# nuksh.net
KiCad netlist of a schematic drawn in EAGLE
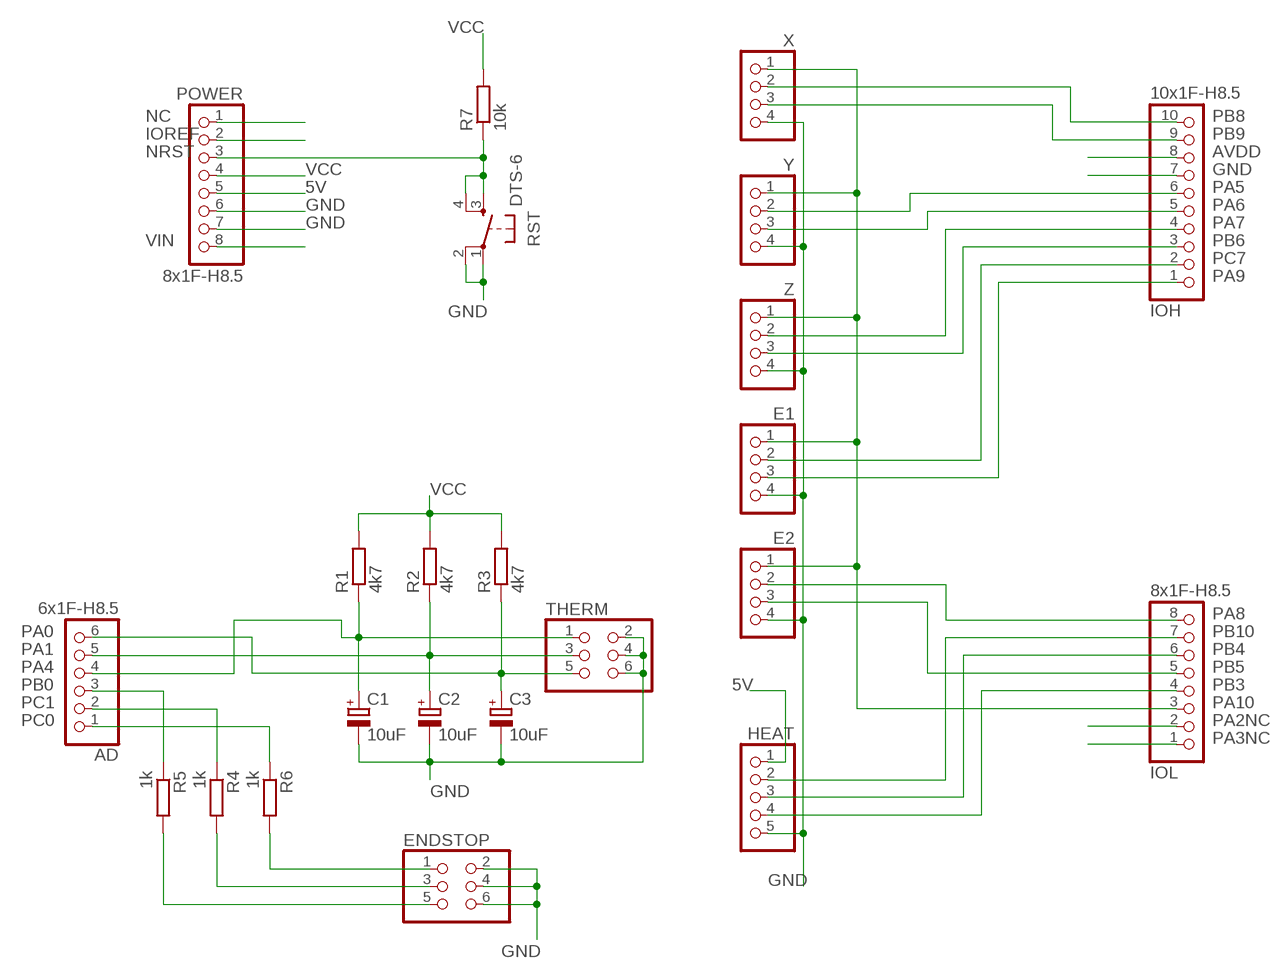
[diagram p0: schematic, sheet 1]

(export (version "E")
  (design (tool "Eeschema 10.0.6"))
  (components
    (comp (ref "AD")
      (value "6x1F-H8.5")
      (footprint "eagle-import:1X06")
      (libsource (lib "eagle-import") (part "PINHD-1X6"))
    )
    (comp (ref "C1")
      (value "10uF")
      (footprint "eagle-import:153CLV-0605")
      (libsource (lib "eagle-import") (part "CPOL-EU153CLV-0605"))
    )
    (comp (ref "C2")
      (value "10uF")
      (footprint "eagle-import:153CLV-0605")
      (libsource (lib "eagle-import") (part "CPOL-EU153CLV-0605"))
    )
    (comp (ref "C3")
      (value "10uF")
      (footprint "eagle-import:153CLV-0605")
      (libsource (lib "eagle-import") (part "CPOL-EU153CLV-0605"))
    )
    (comp (ref "E1")
      (value "PINHD-1X4")
      (footprint "eagle-import:1X04")
      (libsource (lib "eagle-import") (part "PINHD-1X4"))
    )
    (comp (ref "E2")
      (value "PINHD-1X4")
      (footprint "eagle-import:1X04")
      (libsource (lib "eagle-import") (part "PINHD-1X4"))
    )
    (comp (ref "ENDSTOP")
      (value "PINHD-2X3")
      (footprint "eagle-import:2X03")
      (libsource (lib "eagle-import") (part "PINHD-2X3"))
    )
    (comp (ref "HEAT")
      (value "PINHD-1X5")
      (footprint "eagle-import:1X05")
      (libsource (lib "eagle-import") (part "PINHD-1X5"))
    )
    (comp (ref "IOH")
      (value "10x1F-H8.5")
      (footprint "eagle-import:1X10")
      (libsource (lib "eagle-import") (part "PINHD-1X10_ARD"))
    )
    (comp (ref "IOL")
      (value "8x1F-H8.5")
      (footprint "eagle-import:1X08")
      (libsource (lib "eagle-import") (part "PINHD-1X8"))
    )
    (comp (ref "POWER")
      (value "8x1F-H8.5")
      (footprint "eagle-import:1X08")
      (libsource (lib "eagle-import") (part "PINHD-1X8"))
    )
    (comp (ref "R1")
      (value "4k7")
      (footprint "eagle-import:R0805")
      (libsource (lib "eagle-import") (part "R-EU_R0805"))
    )
    (comp (ref "R2")
      (value "4k7")
      (footprint "eagle-import:R0805")
      (libsource (lib "eagle-import") (part "R-EU_R0805"))
    )
    (comp (ref "R3")
      (value "4k7")
      (footprint "eagle-import:R0805")
      (libsource (lib "eagle-import") (part "R-EU_R0805"))
    )
    (comp (ref "R4")
      (value "1k")
      (footprint "eagle-import:R0805")
      (libsource (lib "eagle-import") (part "R-EU_R0805"))
    )
    (comp (ref "R5")
      (value "1k")
      (footprint "eagle-import:R0805")
      (libsource (lib "eagle-import") (part "R-EU_R0805"))
    )
    (comp (ref "R6")
      (value "1k")
      (footprint "eagle-import:R0805")
      (libsource (lib "eagle-import") (part "R-EU_R0805"))
    )
    (comp (ref "R7")
      (value "10k")
      (footprint "eagle-import:R0805")
      (libsource (lib "eagle-import") (part "R-EU_R0805"))
    )
    (comp (ref "RST")
      (value "DTS-6")
      (footprint "eagle-import:DTS-6")
      (libsource (lib "eagle-import") (part "DTS-6"))
    )
    (comp (ref "THERM")
      (value "PINHD-2X3")
      (footprint "eagle-import:2X03")
      (libsource (lib "eagle-import") (part "PINHD-2X3"))
    )
    (comp (ref "X")
      (value "PINHD-1X4")
      (footprint "eagle-import:1X04")
      (libsource (lib "eagle-import") (part "PINHD-1X4"))
    )
    (comp (ref "Y")
      (value "PINHD-1X4")
      (footprint "eagle-import:1X04")
      (libsource (lib "eagle-import") (part "PINHD-1X4"))
    )
    (comp (ref "Z")
      (value "PINHD-1X4")
      (footprint "eagle-import:1X04")
      (libsource (lib "eagle-import") (part "PINHD-1X4"))
    )
  )
  (nets
    (net (code "1") (name "/5V") (class "Default")
      (node (ref "HEAT") (pin "1") (pinfunction "1_1") (pintype "passive"))
      (node (ref "POWER") (pin "5") (pinfunction "5_5") (pintype "passive"))
    )
    (net (code "2") (name "/AVDD") (class "Default")
      (node (ref "IOH") (pin "8") (pinfunction "8_8") (pintype "passive"))
    )
    (net (code "3") (name "/GND") (class "Default")
      (node (ref "C1") (pin "-") (pinfunction "-_-") (pintype "passive"))
      (node (ref "C2") (pin "-") (pinfunction "-_-") (pintype "passive"))
      (node (ref "C3") (pin "-") (pinfunction "-_-") (pintype "passive"))
      (node (ref "E1") (pin "4") (pinfunction "4_4") (pintype "passive"))
      (node (ref "E2") (pin "4") (pinfunction "4_4") (pintype "passive"))
      (node (ref "ENDSTOP") (pin "2") (pinfunction "2_2") (pintype "passive"))
      (node (ref "ENDSTOP") (pin "4") (pinfunction "4_4") (pintype "passive"))
      (node (ref "ENDSTOP") (pin "6") (pinfunction "6_6") (pintype "passive"))
      (node (ref "HEAT") (pin "5") (pinfunction "5_5") (pintype "passive"))
      (node (ref "IOH") (pin "7") (pinfunction "7_7") (pintype "passive"))
      (node (ref "POWER") (pin "6") (pinfunction "6_6") (pintype "passive"))
      (node (ref "POWER") (pin "7") (pinfunction "7_7") (pintype "passive"))
      (node (ref "RST") (pin "1") (pinfunction "1_1") (pintype "passive"))
      (node (ref "RST") (pin "2") (pinfunction "2_2") (pintype "passive"))
      (node (ref "THERM") (pin "2") (pinfunction "2_2") (pintype "passive"))
      (node (ref "THERM") (pin "4") (pinfunction "4_4") (pintype "passive"))
      (node (ref "THERM") (pin "6") (pinfunction "6_6") (pintype "passive"))
      (node (ref "X") (pin "4") (pinfunction "4_4") (pintype "passive"))
      (node (ref "Y") (pin "4") (pinfunction "4_4") (pintype "passive"))
      (node (ref "Z") (pin "4") (pinfunction "4_4") (pintype "passive"))
    )
    (net (code "4") (name "/IOREF") (class "Default")
      (node (ref "POWER") (pin "2") (pinfunction "2_2") (pintype "passive"))
    )
    (net (code "5") (name "/NC") (class "Default")
      (node (ref "POWER") (pin "1") (pinfunction "1_1") (pintype "passive"))
    )
    (net (code "6") (name "/NRST") (class "Default")
      (node (ref "POWER") (pin "3") (pinfunction "3_3") (pintype "passive"))
      (node (ref "R7") (pin "1") (pinfunction "1_1") (pintype "passive"))
      (node (ref "RST") (pin "3") (pinfunction "3_3") (pintype "passive"))
      (node (ref "RST") (pin "4") (pinfunction "4_4") (pintype "passive"))
    )
    (net (code "7") (name "/PA0") (class "Default")
      (node (ref "AD") (pin "4") (pinfunction "4_4") (pintype "passive"))
      (node (ref "C1") (pin "+") (pinfunction "+_+") (pintype "passive"))
      (node (ref "R1") (pin "1") (pinfunction "1_1") (pintype "passive"))
      (node (ref "THERM") (pin "1") (pinfunction "1_1") (pintype "passive"))
    )
    (net (code "8") (name "/PA1") (class "Default")
      (node (ref "AD") (pin "5") (pinfunction "5_5") (pintype "passive"))
      (node (ref "C2") (pin "+") (pinfunction "+_+") (pintype "passive"))
      (node (ref "R2") (pin "1") (pinfunction "1_1") (pintype "passive"))
      (node (ref "THERM") (pin "3") (pinfunction "3_3") (pintype "passive"))
    )
    (net (code "9") (name "/PA2NC") (class "Default")
      (node (ref "IOL") (pin "2") (pinfunction "2_2") (pintype "passive"))
    )
    (net (code "10") (name "/PA3NC") (class "Default")
      (node (ref "IOL") (pin "1") (pinfunction "1_1") (pintype "passive"))
    )
    (net (code "11") (name "/PA4") (class "Default")
      (node (ref "AD") (pin "6") (pinfunction "6_6") (pintype "passive"))
      (node (ref "C3") (pin "+") (pinfunction "+_+") (pintype "passive"))
      (node (ref "R3") (pin "1") (pinfunction "1_1") (pintype "passive"))
      (node (ref "THERM") (pin "5") (pinfunction "5_5") (pintype "passive"))
    )
    (net (code "12") (name "/PA5") (class "Default")
      (node (ref "IOH") (pin "6") (pinfunction "6_6") (pintype "passive"))
      (node (ref "Y") (pin "2") (pinfunction "2_2") (pintype "passive"))
    )
    (net (code "13") (name "/PA6") (class "Default")
      (node (ref "IOH") (pin "5") (pinfunction "5_5") (pintype "passive"))
      (node (ref "Y") (pin "3") (pinfunction "3_3") (pintype "passive"))
    )
    (net (code "14") (name "/PA7") (class "Default")
      (node (ref "IOH") (pin "4") (pinfunction "4_4") (pintype "passive"))
      (node (ref "Z") (pin "2") (pinfunction "2_2") (pintype "passive"))
    )
    (net (code "15") (name "/PA8") (class "Default")
      (node (ref "E2") (pin "2") (pinfunction "2_2") (pintype "passive"))
      (node (ref "IOL") (pin "8") (pinfunction "8_8") (pintype "passive"))
    )
    (net (code "16") (name "/PA9") (class "Default")
      (node (ref "E1") (pin "3") (pinfunction "3_3") (pintype "passive"))
      (node (ref "IOH") (pin "1") (pinfunction "1_1") (pintype "passive"))
    )
    (net (code "17") (name "/PA10") (class "Default")
      (node (ref "E1") (pin "1") (pinfunction "1_1") (pintype "passive"))
      (node (ref "E2") (pin "1") (pinfunction "1_1") (pintype "passive"))
      (node (ref "IOL") (pin "3") (pinfunction "3_3") (pintype "passive"))
      (node (ref "X") (pin "1") (pinfunction "1_1") (pintype "passive"))
      (node (ref "Y") (pin "1") (pinfunction "1_1") (pintype "passive"))
      (node (ref "Z") (pin "1") (pinfunction "1_1") (pintype "passive"))
    )
    (net (code "18") (name "/PB0") (class "Default")
      (node (ref "AD") (pin "3") (pinfunction "3_3") (pintype "passive"))
      (node (ref "R5") (pin "1") (pinfunction "1_1") (pintype "passive"))
    )
    (net (code "19") (name "/PB3") (class "Default")
      (node (ref "HEAT") (pin "4") (pinfunction "4_4") (pintype "passive"))
      (node (ref "IOL") (pin "4") (pinfunction "4_4") (pintype "passive"))
    )
    (net (code "20") (name "/PB4") (class "Default")
      (node (ref "HEAT") (pin "3") (pinfunction "3_3") (pintype "passive"))
      (node (ref "IOL") (pin "6") (pinfunction "6_6") (pintype "passive"))
    )
    (net (code "21") (name "/PB5") (class "Default")
      (node (ref "E2") (pin "3") (pinfunction "3_3") (pintype "passive"))
      (node (ref "IOL") (pin "5") (pinfunction "5_5") (pintype "passive"))
    )
    (net (code "22") (name "/PB6") (class "Default")
      (node (ref "IOH") (pin "3") (pinfunction "3_3") (pintype "passive"))
      (node (ref "Z") (pin "3") (pinfunction "3_3") (pintype "passive"))
    )
    (net (code "23") (name "/PB8") (class "Default")
      (node (ref "IOH") (pin "10") (pinfunction "10_10") (pintype "passive"))
      (node (ref "X") (pin "2") (pinfunction "2_2") (pintype "passive"))
    )
    (net (code "24") (name "/PB9") (class "Default")
      (node (ref "IOH") (pin "9") (pinfunction "9_9") (pintype "passive"))
      (node (ref "X") (pin "3") (pinfunction "3_3") (pintype "passive"))
    )
    (net (code "25") (name "/PB10") (class "Default")
      (node (ref "HEAT") (pin "2") (pinfunction "2_2") (pintype "passive"))
      (node (ref "IOL") (pin "7") (pinfunction "7_7") (pintype "passive"))
    )
    (net (code "26") (name "/PC0") (class "Default")
      (node (ref "AD") (pin "1") (pinfunction "1_1") (pintype "passive"))
      (node (ref "R6") (pin "1") (pinfunction "1_1") (pintype "passive"))
    )
    (net (code "27") (name "/PC1") (class "Default")
      (node (ref "AD") (pin "2") (pinfunction "2_2") (pintype "passive"))
      (node (ref "R4") (pin "1") (pinfunction "1_1") (pintype "passive"))
    )
    (net (code "28") (name "/PC7") (class "Default")
      (node (ref "E1") (pin "2") (pinfunction "2_2") (pintype "passive"))
      (node (ref "IOH") (pin "2") (pinfunction "2_2") (pintype "passive"))
    )
    (net (code "29") (name "/VCC") (class "Default")
      (node (ref "POWER") (pin "4") (pinfunction "4_4") (pintype "passive"))
      (node (ref "R1") (pin "2") (pinfunction "2_2") (pintype "passive"))
      (node (ref "R2") (pin "2") (pinfunction "2_2") (pintype "passive"))
      (node (ref "R3") (pin "2") (pinfunction "2_2") (pintype "passive"))
      (node (ref "R7") (pin "2") (pinfunction "2_2") (pintype "passive"))
    )
    (net (code "30") (name "/VIN") (class "Default")
      (node (ref "POWER") (pin "8") (pinfunction "8_8") (pintype "passive"))
    )
    (net (code "31") (name "Net-(ENDSTOP-Pad1)") (class "Default")
      (node (ref "ENDSTOP") (pin "1") (pinfunction "1_1") (pintype "passive"))
      (node (ref "R6") (pin "2") (pinfunction "2_2") (pintype "passive"))
    )
    (net (code "32") (name "Net-(ENDSTOP-Pad3)") (class "Default")
      (node (ref "ENDSTOP") (pin "3") (pinfunction "3_3") (pintype "passive"))
      (node (ref "R4") (pin "2") (pinfunction "2_2") (pintype "passive"))
    )
    (net (code "33") (name "Net-(ENDSTOP-Pad5)") (class "Default")
      (node (ref "ENDSTOP") (pin "5") (pinfunction "5_5") (pintype "passive"))
      (node (ref "R5") (pin "2") (pinfunction "2_2") (pintype "passive"))
    )
  )
)
